# tick-pi-mk-1_1.net
KiCad netlist of a schematic drawn in EAGLE
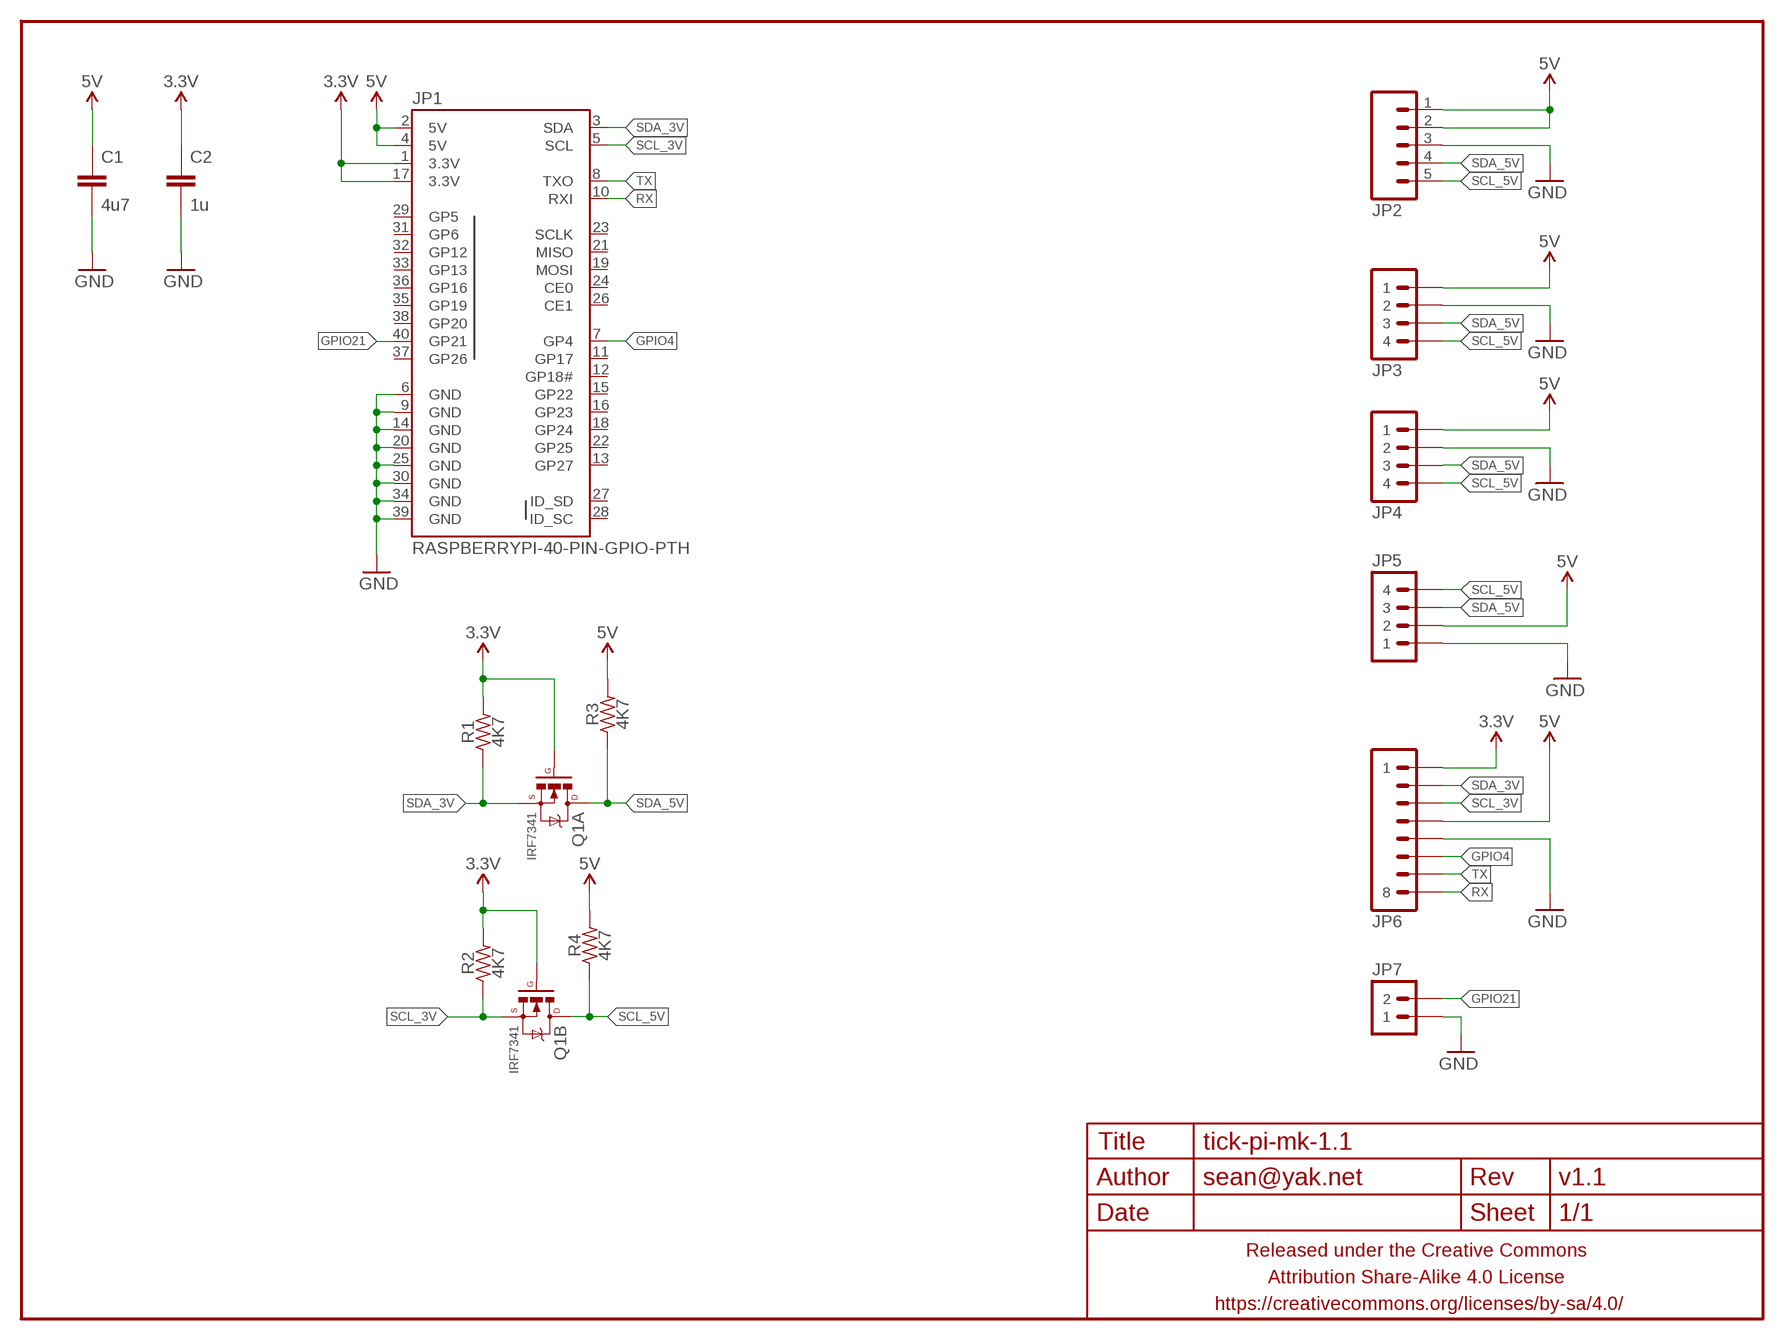
[diagram p0: schematic, sheet 1]

(export (version "E")
  (design (tool "Eeschema 10.0.6"))
  (components
    (comp (ref "C1")
      (value "4u7")
      (footprint "eagle-import:C0805-TIGHTER")
      (libsource (lib "eagle-import") (part "CAPACITOR-CERAMICC0805-TIGHTER"))
    )
    (comp (ref "C2")
      (value "1u")
      (footprint "eagle-import:C0603-TIGHTER")
      (libsource (lib "eagle-import") (part "CAPACITOR-CERAMICC0603-TIGHTER"))
    )
    (comp (ref "FRAME1")
      (value "FRAME-LETTERNO_PACKAGE")
      (footprint "eagle-import:DUMMY")
      (fields (field (name "DESIGNER") "sean@yak.net") (field (name "VERSION") "v1.1"))
      (libsource (lib "eagle-import") (part "FRAME-LETTERNO_PACKAGE"))
    )
    (comp (ref "JP1")
      (value "RASPBERRYPI-40-PIN-GPIO-PTH")
      (footprint "eagle-import:2X20_PTH")
      (libsource (lib "eagle-import") (part "RASPBERRYPI-40-PIN-GPIO-PTH"))
    )
    (comp (ref "JP2")
      (value "M05PTH-CENTERED-RA-FEMALE")
      (footprint "eagle-import:1X05_PTH_CENTERED_RA_FEMALE")
      (libsource (lib "eagle-import") (part "M05PTH-CENTERED-RA-FEMALE"))
    )
    (comp (ref "JP3")
      (value "M04PTH")
      (footprint "eagle-import:1X04-PTH-VERT")
      (libsource (lib "eagle-import") (part "M04PTH"))
    )
    (comp (ref "JP4")
      (value "M04PTH")
      (footprint "eagle-import:1X04-PTH-VERT")
      (libsource (lib "eagle-import") (part "M04PTH"))
    )
    (comp (ref "JP5")
      (value "M04PTH")
      (footprint "eagle-import:1X04-PTH-VERT")
      (libsource (lib "eagle-import") (part "M04PTH"))
    )
    (comp (ref "JP6")
      (value "M081X08")
      (footprint "eagle-import:1X08")
      (libsource (lib "eagle-import") (part "M081X08"))
    )
    (comp (ref "JP7")
      (value "M02PTH-CENTERED")
      (footprint "eagle-import:1X02-CENTER")
      (libsource (lib "eagle-import") (part "M02PTH-CENTERED"))
    )
    (comp (ref "Q1")
      (value "IRF7341")
      (footprint "eagle-import:SO08")
      (libsource (lib "eagle-import") (part "MOSFET-NCHANNEL-DUALSOIC8"))
    )
    (comp (ref "R1")
      (value "4K7")
      (footprint "eagle-import:R0603")
      (libsource (lib "eagle-import") (part "RESISTORR0603"))
    )
    (comp (ref "R2")
      (value "4K7")
      (footprint "eagle-import:R0603")
      (libsource (lib "eagle-import") (part "RESISTORR0603"))
    )
    (comp (ref "R3")
      (value "4K7")
      (footprint "eagle-import:R0603")
      (libsource (lib "eagle-import") (part "RESISTORR0603"))
    )
    (comp (ref "R4")
      (value "4K7")
      (footprint "eagle-import:R0603")
      (libsource (lib "eagle-import") (part "RESISTORR0603"))
    )
  )
  (nets
    (net (code "1") (name "3.3V") (class "Default")
      (node (ref "C2") (pin "1") (pinfunction "1_1") (pintype "passive"))
      (node (ref "JP1") (pin "1") (pinfunction "3.3V_1") (pintype "power_in"))
      (node (ref "JP1") (pin "17") (pinfunction "3.3V_17") (pintype "power_in"))
      (node (ref "JP6") (pin "1") (pinfunction "1_1") (pintype "passive"))
      (node (ref "Q1") (pin "2") (pinfunction "G_2") (pintype "passive"))
      (node (ref "Q1") (pin "4") (pinfunction "G_4") (pintype "passive"))
      (node (ref "R1") (pin "2") (pinfunction "2_2") (pintype "passive"))
      (node (ref "R2") (pin "2") (pinfunction "2_2") (pintype "passive"))
    )
    (net (code "2") (name "5V") (class "Default")
      (node (ref "C1") (pin "1") (pinfunction "1_1") (pintype "passive"))
      (node (ref "JP1") (pin "2") (pinfunction "5V_2") (pintype "power_in"))
      (node (ref "JP1") (pin "4") (pinfunction "5V_4") (pintype "power_in"))
      (node (ref "JP2") (pin "1") (pinfunction "1_1") (pintype "passive"))
      (node (ref "JP2") (pin "2") (pinfunction "2_2") (pintype "passive"))
      (node (ref "JP3") (pin "1") (pinfunction "1_1") (pintype "passive"))
      (node (ref "JP4") (pin "1") (pinfunction "1_1") (pintype "passive"))
      (node (ref "JP5") (pin "2") (pinfunction "2_2") (pintype "passive"))
      (node (ref "JP6") (pin "4") (pinfunction "4_4") (pintype "passive"))
      (node (ref "R3") (pin "2") (pinfunction "2_2") (pintype "passive"))
      (node (ref "R4") (pin "2") (pinfunction "2_2") (pintype "passive"))
    )
    (net (code "3") (name "GND") (class "Default")
      (node (ref "C1") (pin "2") (pinfunction "2_2") (pintype "passive"))
      (node (ref "C2") (pin "2") (pinfunction "2_2") (pintype "passive"))
      (node (ref "JP1") (pin "14") (pinfunction "GND_14") (pintype "power_in"))
      (node (ref "JP1") (pin "20") (pinfunction "GND_20") (pintype "power_in"))
      (node (ref "JP1") (pin "25") (pinfunction "GND_25") (pintype "power_in"))
      (node (ref "JP1") (pin "30") (pinfunction "GND_30") (pintype "power_in"))
      (node (ref "JP1") (pin "34") (pinfunction "GND_34") (pintype "power_in"))
      (node (ref "JP1") (pin "39") (pinfunction "GND_39") (pintype "power_in"))
      (node (ref "JP1") (pin "6") (pinfunction "GND_6") (pintype "power_in"))
      (node (ref "JP1") (pin "9") (pinfunction "GND_9") (pintype "power_in"))
      (node (ref "JP2") (pin "3") (pinfunction "3_3") (pintype "passive"))
      (node (ref "JP3") (pin "2") (pinfunction "2_2") (pintype "passive"))
      (node (ref "JP4") (pin "2") (pinfunction "2_2") (pintype "passive"))
      (node (ref "JP5") (pin "1") (pinfunction "1_1") (pintype "passive"))
      (node (ref "JP6") (pin "5") (pinfunction "5_5") (pintype "passive"))
      (node (ref "JP7") (pin "1") (pinfunction "1_1") (pintype "passive"))
    )
    (net (code "4") (name "GPIO4") (class "Default")
      (node (ref "JP1") (pin "7") (pinfunction "GP4_7") (pintype "bidirectional"))
      (node (ref "JP6") (pin "6") (pinfunction "6_6") (pintype "passive"))
    )
    (net (code "5") (name "GPIO21") (class "Default")
      (node (ref "JP1") (pin "40") (pinfunction "GP21_40") (pintype "bidirectional"))
      (node (ref "JP7") (pin "2") (pinfunction "2_2") (pintype "passive"))
    )
    (net (code "6") (name "RX") (class "Default")
      (node (ref "JP1") (pin "10") (pinfunction "RXI_10") (pintype "input"))
      (node (ref "JP6") (pin "8") (pinfunction "8_8") (pintype "passive"))
    )
    (net (code "7") (name "SCL_3V") (class "Default")
      (node (ref "JP1") (pin "5") (pinfunction "SCL_5") (pintype "bidirectional"))
      (node (ref "JP6") (pin "3") (pinfunction "3_3") (pintype "passive"))
      (node (ref "Q1") (pin "3") (pinfunction "S_3") (pintype "passive"))
      (node (ref "R2") (pin "1") (pinfunction "1_1") (pintype "passive"))
    )
    (net (code "8") (name "SCL_5V") (class "Default")
      (node (ref "JP2") (pin "5") (pinfunction "5_5") (pintype "passive"))
      (node (ref "JP3") (pin "4") (pinfunction "4_4") (pintype "passive"))
      (node (ref "JP4") (pin "4") (pinfunction "4_4") (pintype "passive"))
      (node (ref "JP5") (pin "4") (pinfunction "4_4") (pintype "passive"))
      (node (ref "Q1") (pin "5") (pinfunction "D_5") (pintype "passive"))
      (node (ref "Q1") (pin "6") (pinfunction "D_6") (pintype "passive"))
      (node (ref "R4") (pin "1") (pinfunction "1_1") (pintype "passive"))
    )
    (net (code "9") (name "SDA_3V") (class "Default")
      (node (ref "JP1") (pin "3") (pinfunction "SDA_3") (pintype "bidirectional"))
      (node (ref "JP6") (pin "2") (pinfunction "2_2") (pintype "passive"))
      (node (ref "Q1") (pin "1") (pinfunction "S_1") (pintype "passive"))
      (node (ref "R1") (pin "1") (pinfunction "1_1") (pintype "passive"))
    )
    (net (code "10") (name "SDA_5V") (class "Default")
      (node (ref "JP2") (pin "4") (pinfunction "4_4") (pintype "passive"))
      (node (ref "JP3") (pin "3") (pinfunction "3_3") (pintype "passive"))
      (node (ref "JP4") (pin "3") (pinfunction "3_3") (pintype "passive"))
      (node (ref "JP5") (pin "3") (pinfunction "3_3") (pintype "passive"))
      (node (ref "Q1") (pin "7") (pinfunction "D_7") (pintype "passive"))
      (node (ref "Q1") (pin "8") (pinfunction "D_8") (pintype "passive"))
      (node (ref "R3") (pin "1") (pinfunction "1_1") (pintype "passive"))
    )
    (net (code "11") (name "TX") (class "Default")
      (node (ref "JP1") (pin "8") (pinfunction "TXO_8") (pintype "output"))
      (node (ref "JP6") (pin "7") (pinfunction "7_7") (pintype "passive"))
    )
    (net (code "12") (name "unconnected-(JP1-CE0-Pad24)") (class "Default")
      (node (ref "JP1") (pin "24") (pinfunction "CE0_24") (pintype "output"))
    )
    (net (code "13") (name "unconnected-(JP1-CE1-Pad26)") (class "Default")
      (node (ref "JP1") (pin "26") (pinfunction "CE1_26") (pintype "output"))
    )
    (net (code "14") (name "unconnected-(JP1-GP5-Pad29)") (class "Default")
      (node (ref "JP1") (pin "29") (pinfunction "GP5_29") (pintype "bidirectional"))
    )
    (net (code "15") (name "unconnected-(JP1-GP6-Pad31)") (class "Default")
      (node (ref "JP1") (pin "31") (pinfunction "GP6_31") (pintype "bidirectional"))
    )
    (net (code "16") (name "unconnected-(JP1-GP12-Pad32)") (class "Default")
      (node (ref "JP1") (pin "32") (pinfunction "GP12_32") (pintype "bidirectional"))
    )
    (net (code "17") (name "unconnected-(JP1-GP13-Pad33)") (class "Default")
      (node (ref "JP1") (pin "33") (pinfunction "GP13_33") (pintype "bidirectional"))
    )
    (net (code "18") (name "unconnected-(JP1-GP16-Pad36)") (class "Default")
      (node (ref "JP1") (pin "36") (pinfunction "GP16_36") (pintype "bidirectional"))
    )
    (net (code "19") (name "unconnected-(JP1-GP17-Pad11)") (class "Default")
      (node (ref "JP1") (pin "11") (pinfunction "GP17_11") (pintype "bidirectional"))
    )
    (net (code "20") (name "unconnected-(JP1-GP18#-Pad12)") (class "Default")
      (node (ref "JP1") (pin "12") (pinfunction "GP18#_12") (pintype "bidirectional"))
    )
    (net (code "21") (name "unconnected-(JP1-GP19-Pad35)") (class "Default")
      (node (ref "JP1") (pin "35") (pinfunction "GP19_35") (pintype "bidirectional"))
    )
    (net (code "22") (name "unconnected-(JP1-GP20-Pad38)") (class "Default")
      (node (ref "JP1") (pin "38") (pinfunction "GP20_38") (pintype "bidirectional"))
    )
    (net (code "23") (name "unconnected-(JP1-GP22-Pad15)") (class "Default")
      (node (ref "JP1") (pin "15") (pinfunction "GP22_15") (pintype "bidirectional"))
    )
    (net (code "24") (name "unconnected-(JP1-GP23-Pad16)") (class "Default")
      (node (ref "JP1") (pin "16") (pinfunction "GP23_16") (pintype "bidirectional"))
    )
    (net (code "25") (name "unconnected-(JP1-GP24-Pad18)") (class "Default")
      (node (ref "JP1") (pin "18") (pinfunction "GP24_18") (pintype "bidirectional"))
    )
    (net (code "26") (name "unconnected-(JP1-GP25-Pad22)") (class "Default")
      (node (ref "JP1") (pin "22") (pinfunction "GP25_22") (pintype "bidirectional"))
    )
    (net (code "27") (name "unconnected-(JP1-GP26-Pad37)") (class "Default")
      (node (ref "JP1") (pin "37") (pinfunction "GP26_37") (pintype "bidirectional"))
    )
    (net (code "28") (name "unconnected-(JP1-GP27-Pad13)") (class "Default")
      (node (ref "JP1") (pin "13") (pinfunction "GP27_13") (pintype "bidirectional"))
    )
    (net (code "29") (name "unconnected-(JP1-ID_SC-Pad28)") (class "Default")
      (node (ref "JP1") (pin "28") (pinfunction "ID_SC_28") (pintype "bidirectional"))
    )
    (net (code "30") (name "unconnected-(JP1-ID_SD-Pad27)") (class "Default")
      (node (ref "JP1") (pin "27") (pinfunction "ID_SD_27") (pintype "bidirectional"))
    )
    (net (code "31") (name "unconnected-(JP1-MISO-Pad21)") (class "Default")
      (node (ref "JP1") (pin "21") (pinfunction "MISO_21") (pintype "input"))
    )
    (net (code "32") (name "unconnected-(JP1-MOSI-Pad19)") (class "Default")
      (node (ref "JP1") (pin "19") (pinfunction "MOSI_19") (pintype "output"))
    )
    (net (code "33") (name "unconnected-(JP1-SCLK-Pad23)") (class "Default")
      (node (ref "JP1") (pin "23") (pinfunction "SCLK_23") (pintype "output"))
    )
  )
)
